# firefan.net
KiCad netlist of a schematic drawn in EAGLE
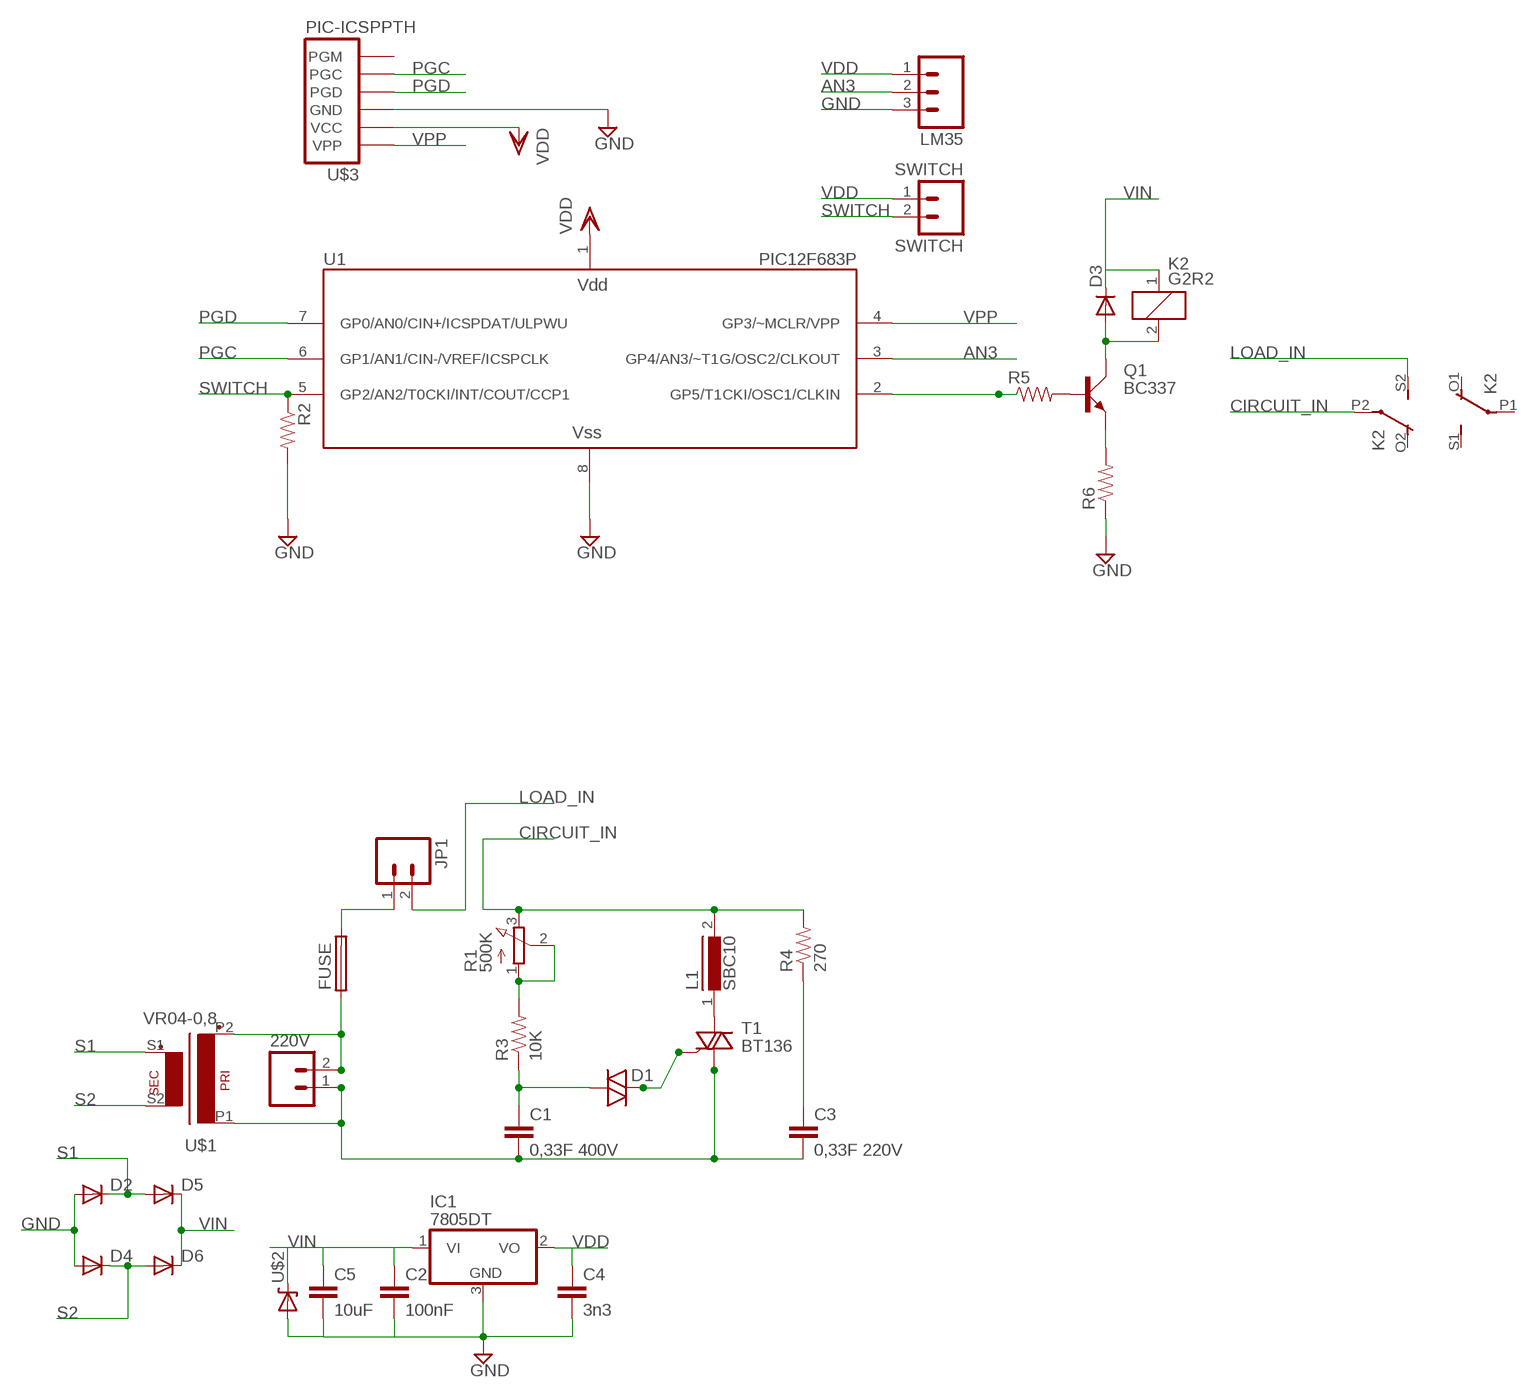
[diagram p0: schematic, sheet 1]

(export (version "E")
  (design (tool "Eeschema 10.0.6"))
  (components
    (comp (ref "220V")
      (value "M023.5MM-NO_SILK")
      (footprint "eagle-import:SCREWTERMINAL-3.5MM-2-NS")
      (libsource (lib "eagle-import") (part "M023.5MM-NO_SILK"))
    )
    (comp (ref "C1")
      (value "0,33F 400V")
      (footprint "eagle-import:CAP-PTH-5MM")
      (libsource (lib "eagle-import") (part "CAPPTH1"))
    )
    (comp (ref "C2")
      (value "100nF")
      (footprint "eagle-import:CAP-PTH-5MM")
      (libsource (lib "eagle-import") (part "CAPPTH1"))
    )
    (comp (ref "C3")
      (value "0,33F 220V")
      (footprint "eagle-import:CAP-PTH-5MM")
      (libsource (lib "eagle-import") (part "CAPPTH1"))
    )
    (comp (ref "C4")
      (value "3n3")
      (footprint "eagle-import:CAP-PTH-5MM")
      (libsource (lib "eagle-import") (part "CAPPTH1"))
    )
    (comp (ref "C5")
      (value "10uF")
      (footprint "eagle-import:CAP-PTH-5MM")
      (libsource (lib "eagle-import") (part "CAPPTH1"))
    )
    (comp (ref "D1")
      (value "DIAC-DO35-10")
      (footprint "eagle-import:DO35-10")
      (libsource (lib "eagle-import") (part "DIAC-DO35-10"))
    )
    (comp (ref "D2")
      (value "1N4004")
      (footprint "eagle-import:DO41-10")
      (libsource (lib "eagle-import") (part "1N4004"))
    )
    (comp (ref "D3")
      (value "1N4004")
      (footprint "eagle-import:DO41-10")
      (libsource (lib "eagle-import") (part "1N4004"))
    )
    (comp (ref "D4")
      (value "1N4004")
      (footprint "eagle-import:DO41-10")
      (libsource (lib "eagle-import") (part "1N4004"))
    )
    (comp (ref "D5")
      (value "1N4004")
      (footprint "eagle-import:DO41-10")
      (libsource (lib "eagle-import") (part "1N4004"))
    )
    (comp (ref "D6")
      (value "1N4004")
      (footprint "eagle-import:DO41-10")
      (libsource (lib "eagle-import") (part "1N4004"))
    )
    (comp (ref "FUSE")
      (value "SH22,5A")
      (footprint "eagle-import:SH22,5A")
      (fields (field (name "MPN") "0031.7701.11"))
      (libsource (lib "eagle-import") (part "SH22,5A"))
    )
    (comp (ref "IC1")
      (value "7805DT")
      (footprint "eagle-import:TO252")
      (libsource (lib "eagle-import") (part "78DT05"))
    )
    (comp (ref "JP1")
      (value "M023.5MM-NO_SILK")
      (footprint "eagle-import:SCREWTERMINAL-3.5MM-2-NS")
      (libsource (lib "eagle-import") (part "M023.5MM-NO_SILK"))
    )
    (comp (ref "K2")
      (value "G2R2")
      (footprint "eagle-import:G2R2")
      (fields (field (name "MF") "OMRON COMPONENTS USA") (field (name "MPN") "G2R-2-DC6"))
      (libsource (lib "eagle-import") (part "G2R2"))
    )
    (comp (ref "L1")
      (value "SBC10")
      (footprint "eagle-import:SBC10")
      (libsource (lib "eagle-import") (part "SBC10"))
    )
    (comp (ref "LM35")
      (value "M03LONGPADS")
      (footprint "eagle-import:1X03_LONGPADS")
      (libsource (lib "eagle-import") (part "M03LONGPADS"))
    )
    (comp (ref "Q1")
      (value "BC337")
      (footprint "eagle-import:SOT54A")
      (libsource (lib "eagle-import") (part "BC337"))
    )
    (comp (ref "R1")
      (value "500K")
      (footprint "eagle-import:3RP_1610N")
      (libsource (lib "eagle-import") (part "3RP/1610N"))
    )
    (comp (ref "R2")
      (value "RESISTORPTH-1/4W")
      (footprint "eagle-import:AXIAL-0.4")
      (libsource (lib "eagle-import") (part "RESISTORPTH-1/4W"))
    )
    (comp (ref "R3")
      (value "10K")
      (footprint "eagle-import:AXIAL-0.5")
      (libsource (lib "eagle-import") (part "RESISTORPTH-1/2W"))
    )
    (comp (ref "R4")
      (value "270")
      (footprint "eagle-import:AXIAL-0.5")
      (libsource (lib "eagle-import") (part "RESISTORPTH-1/2W"))
    )
    (comp (ref "R5")
      (value "RESISTORPTH-1/4W")
      (footprint "eagle-import:AXIAL-0.4")
      (libsource (lib "eagle-import") (part "RESISTORPTH-1/4W"))
    )
    (comp (ref "R6")
      (value "RESISTORPTH-1/4W")
      (footprint "eagle-import:AXIAL-0.4")
      (libsource (lib "eagle-import") (part "RESISTORPTH-1/4W"))
    )
    (comp (ref "SWITCH")
      (value "SWITCH")
      (footprint "eagle-import:SCREWTERMINAL-3.5MM-2-NS")
      (libsource (lib "eagle-import") (part "M023.5MM-NO_SILK"))
    )
    (comp (ref "T1")
      (value "BT136")
      (footprint "eagle-import:TO220AB")
      (libsource (lib "eagle-import") (part "BT136"))
    )
    (comp (ref "U$1")
      (value "VR04-0,8")
      (footprint "eagle-import:VR04-0,8")
      (libsource (lib "eagle-import") (part "VR04-0,8"))
    )
    (comp (ref "U$2")
      (value "DIODE-ZENERPTH")
      (footprint "eagle-import:DIODE-ZENER")
      (libsource (lib "eagle-import") (part "DIODE-ZENERPTH"))
    )
    (comp (ref "U$3")
      (value "PIC-ICSPPTH")
      (footprint "eagle-import:MOLEX-1X6")
      (libsource (lib "eagle-import") (part "PIC-ICSPPTH"))
    )
    (comp (ref "U1")
      (value "PIC12F683P")
      (footprint "eagle-import:DIP-8")
      (libsource (lib "eagle-import") (part "PIC12F683P"))
    )
  )
  (nets
    (net (code "1") (name "/AN3") (class "Default")
      (node (ref "LM35") (pin "2") (pinfunction "2_2") (pintype "passive"))
      (node (ref "U1") (pin "3") (pinfunction "GP4/AN3/~{T1G/OSC2/CLKOUT}_3") (pintype "bidirectional"))
    )
    (net (code "2") (name "/CIRCUIT_IN") (class "Default")
      (node (ref "K2") (pin "P2") (pinfunction "P_P2") (pintype "passive"))
      (node (ref "L1") (pin "2") (pinfunction "2_2") (pintype "passive"))
      (node (ref "R1") (pin "3") (pinfunction "E_3") (pintype "passive"))
      (node (ref "R4") (pin "P$2") (pinfunction "2_P$2") (pintype "passive"))
    )
    (net (code "3") (name "/LOAD_IN") (class "Default")
      (node (ref "JP1") (pin "2") (pinfunction "2_2") (pintype "passive"))
      (node (ref "K2") (pin "S2") (pinfunction "S_S2") (pintype "passive"))
    )
    (net (code "4") (name "/PGC") (class "Default")
      (node (ref "U$3") (pin "5") (pinfunction "PGC_5") (pintype "bidirectional"))
      (node (ref "U1") (pin "6") (pinfunction "GP1/AN1/CIN-/VREF/ICSPCLK_6") (pintype "bidirectional"))
    )
    (net (code "5") (name "/PGD") (class "Default")
      (node (ref "U$3") (pin "4") (pinfunction "PGD_4") (pintype "bidirectional"))
      (node (ref "U1") (pin "7") (pinfunction "GP0/AN0/CIN+/ICSPDAT/ULPWU_7") (pintype "bidirectional"))
    )
    (net (code "6") (name "/S1") (class "Default")
      (node (ref "D2") (pin "C") (pinfunction "C_C") (pintype "passive"))
      (node (ref "D5") (pin "A") (pinfunction "A_A") (pintype "passive"))
      (node (ref "U$1") (pin "S1") (pinfunction "S3_S1") (pintype "passive"))
    )
    (net (code "7") (name "/S2") (class "Default")
      (node (ref "D4") (pin "C") (pinfunction "C_C") (pintype "passive"))
      (node (ref "D6") (pin "A") (pinfunction "A_A") (pintype "passive"))
      (node (ref "U$1") (pin "S2") (pinfunction "S4_S2") (pintype "passive"))
    )
    (net (code "8") (name "/SWITCH") (class "Default")
      (node (ref "R2") (pin "P$1") (pinfunction "1_P$1") (pintype "passive"))
      (node (ref "SWITCH") (pin "2") (pinfunction "2_2") (pintype "passive"))
      (node (ref "U1") (pin "5") (pinfunction "GP2/AN2/T0CKI/INT/COUT/CCP1_5") (pintype "bidirectional"))
    )
    (net (code "9") (name "/VIN") (class "Default")
      (node (ref "C2") (pin "1") (pinfunction "1_1") (pintype "passive"))
      (node (ref "C5") (pin "1") (pinfunction "1_1") (pintype "passive"))
      (node (ref "D3") (pin "C") (pinfunction "C_C") (pintype "passive"))
      (node (ref "D5") (pin "C") (pinfunction "C_C") (pintype "passive"))
      (node (ref "D6") (pin "C") (pinfunction "C_C") (pintype "passive"))
      (node (ref "IC1") (pin "1") (pinfunction "VI_1") (pintype "input"))
      (node (ref "K2") (pin "1") (pinfunction "1_1") (pintype "passive"))
      (node (ref "U$2") (pin "P$1") (pinfunction "C_P$1") (pintype "passive"))
    )
    (net (code "10") (name "/VPP") (class "Default")
      (node (ref "U$3") (pin "1") (pinfunction "VPP_1") (pintype "bidirectional"))
      (node (ref "U1") (pin "4") (pinfunction "GP3/~{MCLR/VPP}_4") (pintype "input"))
    )
    (net (code "11") (name "GND") (class "Default")
      (node (ref "C2") (pin "2") (pinfunction "2_2") (pintype "passive"))
      (node (ref "C4") (pin "2") (pinfunction "2_2") (pintype "passive"))
      (node (ref "C5") (pin "2") (pinfunction "2_2") (pintype "passive"))
      (node (ref "D2") (pin "A") (pinfunction "A_A") (pintype "passive"))
      (node (ref "D4") (pin "A") (pinfunction "A_A") (pintype "passive"))
      (node (ref "IC1") (pin "3") (pinfunction "GND_3") (pintype "passive"))
      (node (ref "LM35") (pin "3") (pinfunction "3_3") (pintype "passive"))
      (node (ref "R2") (pin "P$2") (pinfunction "2_P$2") (pintype "passive"))
      (node (ref "R6") (pin "P$1") (pinfunction "1_P$1") (pintype "passive"))
      (node (ref "U$2") (pin "P$2") (pinfunction "A_P$2") (pintype "passive"))
      (node (ref "U$3") (pin "3") (pinfunction "GND_3") (pintype "bidirectional"))
      (node (ref "U1") (pin "8") (pinfunction "VSS_8") (pintype "power_in"))
    )
    (net (code "12") (name "Net-(220V-Pad2)") (class "Default")
      (node (ref "220V") (pin "2") (pinfunction "2_2") (pintype "passive"))
      (node (ref "FUSE") (pin "1") (pinfunction "1_1") (pintype "passive"))
      (node (ref "U$1") (pin "P2") (pinfunction "P2_P2") (pintype "passive"))
    )
    (net (code "13") (name "Net-(D1-1)") (class "Default")
      (node (ref "C1") (pin "1") (pinfunction "1_1") (pintype "passive"))
      (node (ref "D1") (pin "A") (pinfunction "1_A") (pintype "passive"))
      (node (ref "R3") (pin "P$1") (pinfunction "1_P$1") (pintype "passive"))
    )
    (net (code "14") (name "Net-(D1-2)") (class "Default")
      (node (ref "D1") (pin "C") (pinfunction "2_C") (pintype "passive"))
      (node (ref "T1") (pin "3") (pinfunction "G_3") (pintype "passive"))
    )
    (net (code "15") (name "Net-(D3-PadA)") (class "Default")
      (node (ref "D3") (pin "A") (pinfunction "A_A") (pintype "passive"))
      (node (ref "K2") (pin "2") (pinfunction "2_2") (pintype "passive"))
      (node (ref "Q1") (pin "C") (pinfunction "C_C") (pintype "passive"))
    )
    (net (code "16") (name "Net-(FUSE-Pad2)") (class "Default")
      (node (ref "FUSE") (pin "2") (pinfunction "2_2") (pintype "passive"))
      (node (ref "JP1") (pin "1") (pinfunction "1_1") (pintype "passive"))
    )
    (net (code "17") (name "Net-(R1-A)") (class "Default")
      (node (ref "R1") (pin "1") (pinfunction "A_1") (pintype "passive"))
      (node (ref "R1") (pin "2") (pinfunction "S_2") (pintype "passive"))
      (node (ref "R3") (pin "P$2") (pinfunction "2_P$2") (pintype "passive"))
    )
    (net (code "18") (name "Net-(R4-1)") (class "Default")
      (node (ref "C3") (pin "1") (pinfunction "1_1") (pintype "passive"))
      (node (ref "R4") (pin "P$1") (pinfunction "1_P$1") (pintype "passive"))
    )
    (net (code "19") (name "Net-(R5-1)") (class "Default")
      (node (ref "R5") (pin "P$1") (pinfunction "1_P$1") (pintype "passive"))
      (node (ref "U1") (pin "2") (pinfunction "GP5/T1CKI/OSC1/CLKIN_2") (pintype "bidirectional"))
    )
    (net (code "20") (name "Net-(R5-2)") (class "Default")
      (node (ref "Q1") (pin "B") (pinfunction "B_B") (pintype "passive"))
      (node (ref "R5") (pin "P$2") (pinfunction "2_P$2") (pintype "passive"))
    )
    (net (code "21") (name "Net-(R6-2)") (class "Default")
      (node (ref "Q1") (pin "E") (pinfunction "E_E") (pintype "passive"))
      (node (ref "R6") (pin "P$2") (pinfunction "2_P$2") (pintype "passive"))
    )
    (net (code "22") (name "Net-(T1-A1)") (class "Default")
      (node (ref "220V") (pin "1") (pinfunction "1_1") (pintype "passive"))
      (node (ref "C1") (pin "2") (pinfunction "2_2") (pintype "passive"))
      (node (ref "C3") (pin "2") (pinfunction "2_2") (pintype "passive"))
      (node (ref "T1") (pin "1") (pinfunction "A1_1") (pintype "passive"))
      (node (ref "U$1") (pin "P1") (pinfunction "P1_P1") (pintype "passive"))
    )
    (net (code "23") (name "Net-(T1-A2)") (class "Default")
      (node (ref "L1") (pin "1") (pinfunction "1_1") (pintype "passive"))
      (node (ref "T1") (pin "2") (pinfunction "A2_2") (pintype "passive"))
    )
    (net (code "24") (name "VDD") (class "Default")
      (node (ref "C4") (pin "1") (pinfunction "1_1") (pintype "passive"))
      (node (ref "IC1") (pin "2") (pinfunction "VO_2") (pintype "passive"))
      (node (ref "LM35") (pin "1") (pinfunction "1_1") (pintype "passive"))
      (node (ref "SWITCH") (pin "1") (pinfunction "1_1") (pintype "passive"))
      (node (ref "U$3") (pin "2") (pinfunction "VCC_2") (pintype "bidirectional"))
      (node (ref "U1") (pin "1") (pinfunction "VDD_1") (pintype "power_in"))
    )
    (net (code "25") (name "unconnected-(K2B-O-PadO1)") (class "Default")
      (node (ref "K2") (pin "O1") (pinfunction "O_O1") (pintype "passive"))
    )
    (net (code "26") (name "unconnected-(K2B-P-PadP1)") (class "Default")
      (node (ref "K2") (pin "P1") (pinfunction "P_P1") (pintype "passive"))
    )
    (net (code "27") (name "unconnected-(K2B-S-PadS1)") (class "Default")
      (node (ref "K2") (pin "S1") (pinfunction "S_S1") (pintype "passive"))
    )
    (net (code "28") (name "unconnected-(K2C-O-PadO2)") (class "Default")
      (node (ref "K2") (pin "O2") (pinfunction "O_O2") (pintype "passive"))
    )
    (net (code "29") (name "unconnected-(U$3-PGM-Pad6)") (class "Default")
      (node (ref "U$3") (pin "6") (pinfunction "PGM_6") (pintype "bidirectional"))
    )
  )
)
